# 05_LCD_LVDS.net
KiCad netlist of a schematic drawn in Altium Designer
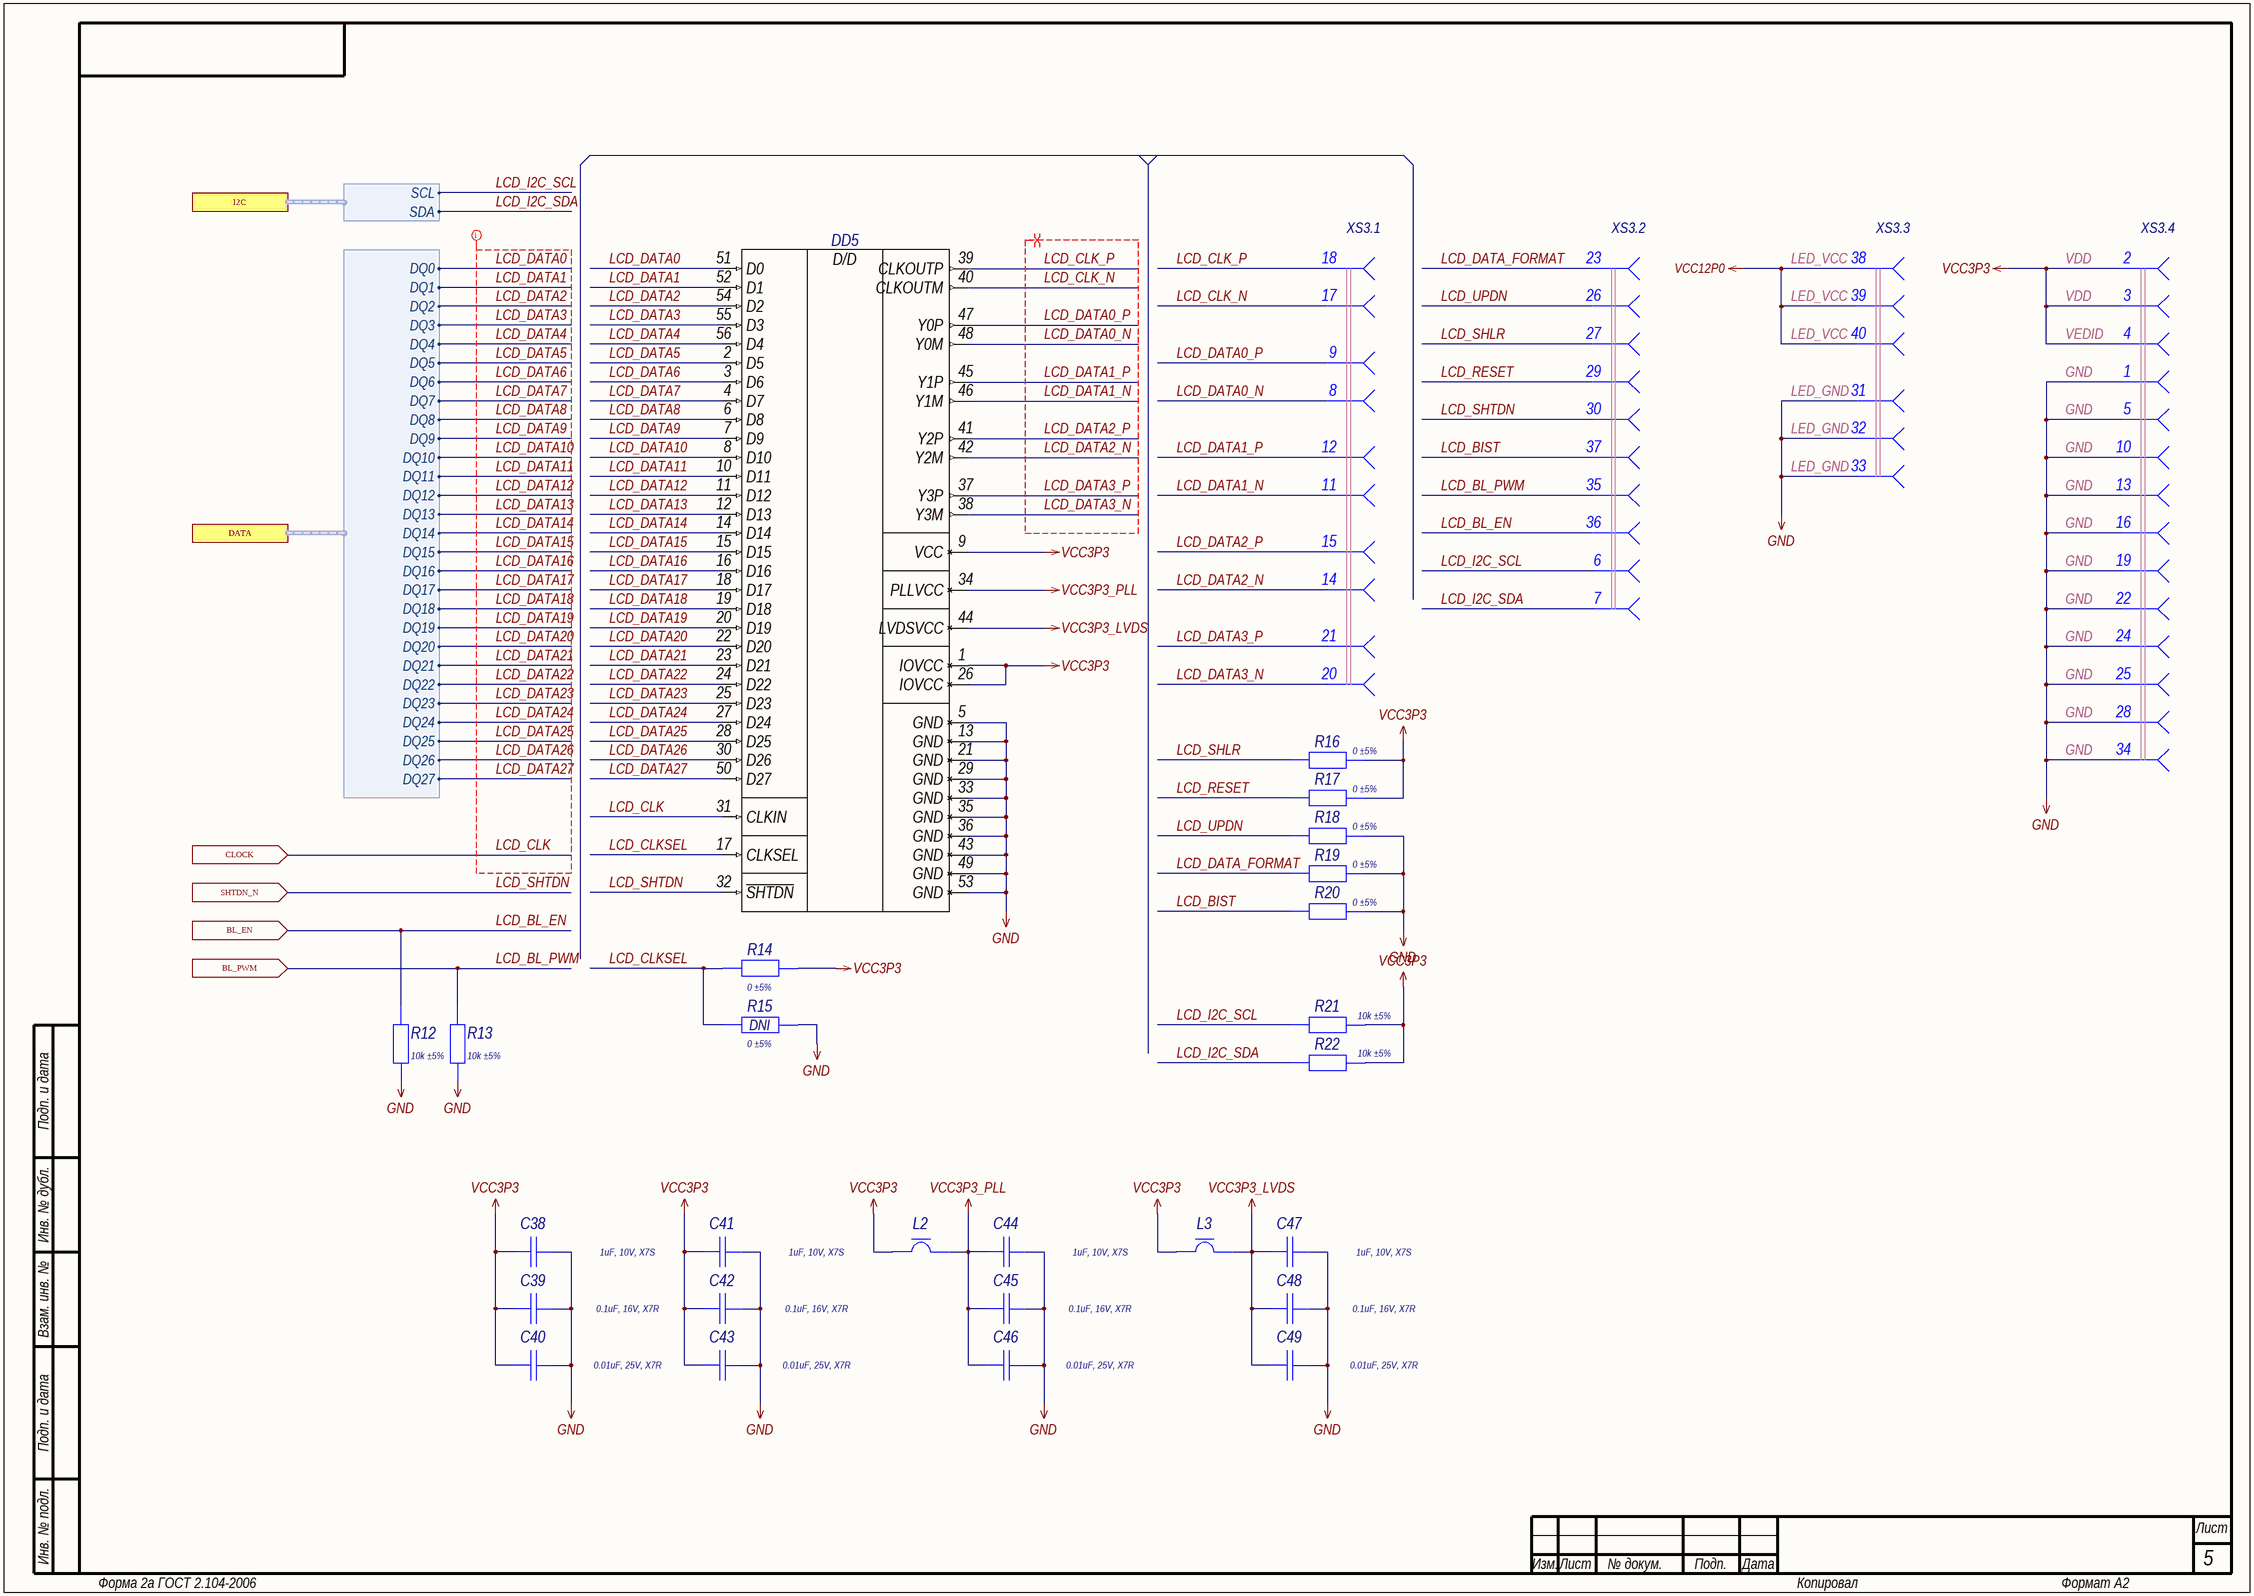
[diagram p0: 05_LCD_LVDS.SchDoc]

(export (version "E")
  (design (tool "Eeschema 10.0.6"))
  (components
    (comp (ref "C38")
      (value "Capacitor")
      (footprint "C0402_L")
      (fields
        (field (name "SCHEMATIC VALUE") "1uF, 10V, X7S")
        (field (name "PART NUMBER") "GRM155C71A105KE11D")
        (field (name "VOLTAGE") "10V")
        (field (name "TOLERANCE") "±10%")
        (field (name "PUBLISHER") "Andrew Danich")
      )
      (libsource (lib "ADLib") (part "Capacitor"))
    )
    (comp (ref "C39")
      (value "Capacitor")
      (footprint "C0402_L")
      (fields
        (field (name "SCHEMATIC VALUE") "0.1uF, 16V, X7R")
        (field (name "PART NUMBER") "GCM155R71C104KA55D")
        (field (name "VOLTAGE") "16V")
        (field (name "TOLERANCE") "±10%")
        (field (name "PUBLISHER") "Andrew Danich")
      )
      (libsource (lib "ADLib") (part "Capacitor"))
    )
    (comp (ref "C40")
      (value "Capacitor")
      (footprint "C0402_L")
      (fields
        (field (name "SCHEMATIC VALUE") "0.01uF, 25V, X7R")
        (field (name "PART NUMBER") "GCM155R71E103KA37D")
        (field (name "VOLTAGE") "25V")
        (field (name "TOLERANCE") "±10%")
        (field (name "PUBLISHER") "Andrew Danich")
      )
      (libsource (lib "ADLib") (part "Capacitor"))
    )
    (comp (ref "C41")
      (value "Capacitor")
      (footprint "C0402_L")
      (fields
        (field (name "SCHEMATIC VALUE") "1uF, 10V, X7S")
        (field (name "PART NUMBER") "GRM155C71A105KE11D")
        (field (name "VOLTAGE") "10V")
        (field (name "TOLERANCE") "±10%")
        (field (name "PUBLISHER") "Andrew Danich")
      )
      (libsource (lib "ADLib") (part "Capacitor"))
    )
    (comp (ref "C42")
      (value "Capacitor")
      (footprint "C0402_L")
      (fields
        (field (name "SCHEMATIC VALUE") "0.1uF, 16V, X7R")
        (field (name "PART NUMBER") "GCM155R71C104KA55D")
        (field (name "VOLTAGE") "16V")
        (field (name "TOLERANCE") "±10%")
        (field (name "PUBLISHER") "Andrew Danich")
      )
      (libsource (lib "ADLib") (part "Capacitor"))
    )
    (comp (ref "C43")
      (value "Capacitor")
      (footprint "C0402_L")
      (fields
        (field (name "SCHEMATIC VALUE") "0.01uF, 25V, X7R")
        (field (name "PART NUMBER") "GCM155R71E103KA37D")
        (field (name "VOLTAGE") "25V")
        (field (name "TOLERANCE") "±10%")
        (field (name "PUBLISHER") "Andrew Danich")
      )
      (libsource (lib "ADLib") (part "Capacitor"))
    )
    (comp (ref "C44")
      (value "Capacitor")
      (footprint "C0402_L")
      (fields
        (field (name "SCHEMATIC VALUE") "1uF, 10V, X7S")
        (field (name "PART NUMBER") "GRM155C71A105KE11D")
        (field (name "VOLTAGE") "10V")
        (field (name "TOLERANCE") "±10%")
        (field (name "PUBLISHER") "Andrew Danich")
      )
      (libsource (lib "ADLib") (part "Capacitor"))
    )
    (comp (ref "C45")
      (value "Capacitor")
      (footprint "C0402_L")
      (fields
        (field (name "SCHEMATIC VALUE") "0.1uF, 16V, X7R")
        (field (name "PART NUMBER") "GCM155R71C104KA55D")
        (field (name "VOLTAGE") "16V")
        (field (name "TOLERANCE") "±10%")
        (field (name "PUBLISHER") "Andrew Danich")
      )
      (libsource (lib "ADLib") (part "Capacitor"))
    )
    (comp (ref "C46")
      (value "Capacitor")
      (footprint "C0402_L")
      (fields
        (field (name "SCHEMATIC VALUE") "0.01uF, 25V, X7R")
        (field (name "PART NUMBER") "GCM155R71E103KA37D")
        (field (name "VOLTAGE") "25V")
        (field (name "TOLERANCE") "±10%")
        (field (name "PUBLISHER") "Andrew Danich")
      )
      (libsource (lib "ADLib") (part "Capacitor"))
    )
    (comp (ref "C47")
      (value "Capacitor")
      (footprint "C0402_L")
      (fields
        (field (name "SCHEMATIC VALUE") "1uF, 10V, X7S")
        (field (name "PART NUMBER") "GRM155C71A105KE11D")
        (field (name "VOLTAGE") "10V")
        (field (name "TOLERANCE") "±10%")
        (field (name "PUBLISHER") "Andrew Danich")
      )
      (libsource (lib "ADLib") (part "Capacitor"))
    )
    (comp (ref "C48")
      (value "Capacitor")
      (footprint "C0402_L")
      (fields
        (field (name "SCHEMATIC VALUE") "0.1uF, 16V, X7R")
        (field (name "PART NUMBER") "GCM155R71C104KA55D")
        (field (name "VOLTAGE") "16V")
        (field (name "TOLERANCE") "±10%")
        (field (name "PUBLISHER") "Andrew Danich")
      )
      (libsource (lib "ADLib") (part "Capacitor"))
    )
    (comp (ref "C49")
      (value "Capacitor")
      (footprint "C0402_L")
      (fields
        (field (name "SCHEMATIC VALUE") "0.01uF, 25V, X7R")
        (field (name "PART NUMBER") "GCM155R71E103KA37D")
        (field (name "VOLTAGE") "25V")
        (field (name "TOLERANCE") "±10%")
        (field (name "PUBLISHER") "Andrew Danich")
      )
      (libsource (lib "ADLib") (part "Capacitor"))
    )
    (comp (ref "DD5")
      (value "SN65LVDS93ADGG")
      (footprint "TSSOP-56_050P1400X610X120_N")
      (fields
        (field (name "PART NUMBER") "SN65LVDS93ADGGR")
        (field (name "MANUFACTURER") "Texas Instruments")
        (field (name "PUBLISHER") "Andrew Danich")
      )
      (libsource (lib "ADLib") (part "SN65LVDS93ADGG"))
    )
    (comp (ref "L2")
      (value "FerriteBead")
      (footprint "L0402_L")
      (fields
        (field (name "PART NUMBER") "BLM15PD121SN1D")
        (field (name "TOLERANCE") "±25%")
        (field (name "MANUFACTURER") "Murata")
        (field (name "PUBLISHER") "Andrew Danich")
      )
      (libsource (lib "ADLib") (part "FerriteBead"))
    )
    (comp (ref "L3")
      (value "FerriteBead")
      (footprint "L0402_L")
      (fields
        (field (name "PART NUMBER") "BLM15PD121SN1D")
        (field (name "TOLERANCE") "±25%")
        (field (name "MANUFACTURER") "Murata")
        (field (name "PUBLISHER") "Andrew Danich")
      )
      (libsource (lib "ADLib") (part "FerriteBead"))
    )
    (comp (ref "R12")
      (value "Resistor")
      (footprint "R0402_L")
      (fields
        (field (name "SCHEMATIC VALUE") "10k ±5%")
        (field (name "PART NUMBER") "RC0402JR-0710KL")
        (field (name "TOLERANCE") "±5%")
        (field (name "MANUFACTURER") "Yageo")
        (field (name "PUBLISHER") "Andrew Danich")
      )
      (libsource (lib "ADLib") (part "Resistor"))
    )
    (comp (ref "R13")
      (value "Resistor")
      (footprint "R0402_L")
      (fields
        (field (name "SCHEMATIC VALUE") "10k ±5%")
        (field (name "PART NUMBER") "RC0402JR-0710KL")
        (field (name "TOLERANCE") "±5%")
        (field (name "MANUFACTURER") "Yageo")
        (field (name "PUBLISHER") "Andrew Danich")
      )
      (libsource (lib "ADLib") (part "Resistor"))
    )
    (comp (ref "R14")
      (value "Resistor")
      (footprint "R0402_L")
      (fields
        (field (name "SCHEMATIC VALUE") "0 ±5%")
        (field (name "PART NUMBER") "RC0402JR-070RL")
        (field (name "TOLERANCE") "±5%")
        (field (name "MANUFACTURER") "Yageo")
        (field (name "PUBLISHER") "Andrew Danich")
      )
      (libsource (lib "ADLib") (part "Resistor"))
    )
    (comp (ref "R15")
      (value "Resistor")
      (footprint "R0402_L")
      (fields
        (field (name "SCHEMATIC VALUE") "0 ±5%")
        (field (name "PART NUMBER") "RC0402JR-070RL")
        (field (name "TOLERANCE") "±5%")
        (field (name "MANUFACTURER") "Yageo")
        (field (name "PUBLISHER") "Andrew Danich")
      )
      (libsource (lib "ADLib") (part "Resistor"))
    )
    (comp (ref "R16")
      (value "Resistor")
      (footprint "R0402_L")
      (fields
        (field (name "SCHEMATIC VALUE") "0 ±5%")
        (field (name "PART NUMBER") "RC0402JR-070RL")
        (field (name "TOLERANCE") "±5%")
        (field (name "MANUFACTURER") "Yageo")
        (field (name "PUBLISHER") "Andrew Danich")
      )
      (libsource (lib "ADLib") (part "Resistor"))
    )
    (comp (ref "R17")
      (value "Resistor")
      (footprint "R0402_L")
      (fields
        (field (name "SCHEMATIC VALUE") "0 ±5%")
        (field (name "PART NUMBER") "RC0402JR-070RL")
        (field (name "TOLERANCE") "±5%")
        (field (name "MANUFACTURER") "Yageo")
        (field (name "PUBLISHER") "Andrew Danich")
      )
      (libsource (lib "ADLib") (part "Resistor"))
    )
    (comp (ref "R18")
      (value "Resistor")
      (footprint "R0402_L")
      (fields
        (field (name "SCHEMATIC VALUE") "0 ±5%")
        (field (name "PART NUMBER") "RC0402JR-070RL")
        (field (name "TOLERANCE") "±5%")
        (field (name "MANUFACTURER") "Yageo")
        (field (name "PUBLISHER") "Andrew Danich")
      )
      (libsource (lib "ADLib") (part "Resistor"))
    )
    (comp (ref "R19")
      (value "Resistor")
      (footprint "R0402_L")
      (fields
        (field (name "SCHEMATIC VALUE") "0 ±5%")
        (field (name "PART NUMBER") "RC0402JR-070RL")
        (field (name "TOLERANCE") "±5%")
        (field (name "MANUFACTURER") "Yageo")
        (field (name "PUBLISHER") "Andrew Danich")
      )
      (libsource (lib "ADLib") (part "Resistor"))
    )
    (comp (ref "R20")
      (value "Resistor")
      (footprint "R0402_L")
      (fields
        (field (name "SCHEMATIC VALUE") "0 ±5%")
        (field (name "PART NUMBER") "RC0402JR-070RL")
        (field (name "TOLERANCE") "±5%")
        (field (name "MANUFACTURER") "Yageo")
        (field (name "PUBLISHER") "Andrew Danich")
      )
      (libsource (lib "ADLib") (part "Resistor"))
    )
    (comp (ref "R21")
      (value "Resistor")
      (footprint "R0402_L")
      (fields
        (field (name "SCHEMATIC VALUE") "10k ±5%")
        (field (name "PART NUMBER") "RC0402JR-0710KL")
        (field (name "TOLERANCE") "±5%")
        (field (name "MANUFACTURER") "Yageo")
        (field (name "PUBLISHER") "Andrew Danich")
      )
      (libsource (lib "ADLib") (part "Resistor"))
    )
    (comp (ref "R22")
      (value "Resistor")
      (footprint "R0402_L")
      (fields
        (field (name "SCHEMATIC VALUE") "10k ±5%")
        (field (name "PART NUMBER") "RC0402JR-0710KL")
        (field (name "TOLERANCE") "±5%")
        (field (name "MANUFACTURER") "Yageo")
        (field (name "PUBLISHER") "Andrew Danich")
      )
      (libsource (lib "ADLib") (part "Resistor"))
    )
    (comp (ref "XS3")
      (value "TFT LVDS")
      (footprint "54104-4031")
      (fields
        (field (name "PART NUMBER") "54104-4031")
        (field (name "MANUFACTURER") "Molex")
        (field (name "PUBLISHER") "Andrew Danich")
      )
      (libsource (lib "ADLib") (part "Con-40-F_S"))
    )
  )
  (nets
    (net (code "3") (name "/LCD_BIST") (class "Default")
      (node (ref "R20") (pin "1") (pinfunction "1_1") (pintype "passive"))
      (node (ref "XS3") (pin "37") (pintype "passive"))
    )
    (net (code "4") (name "/LCD_BL_EN") (class "Default")
      (node (ref "R12") (pin "2") (pinfunction "2_2") (pintype "passive"))
      (node (ref "XS3") (pin "36") (pintype "passive"))
    )
    (net (code "5") (name "/LCD_BL_PWM") (class "Default")
      (node (ref "R13") (pin "2") (pinfunction "2_2") (pintype "passive"))
      (node (ref "XS3") (pin "35") (pintype "passive"))
    )
    (net (code "6") (name "/LCD_CLK") (class "Default")
      (node (ref "DD5") (pin "31") (pinfunction "CLKIN_31") (pintype "input"))
    )
    (net (code "7") (name "/LCD_CLKSEL") (class "Default")
      (node (ref "DD5") (pin "17") (pinfunction "CLKSEL_17") (pintype "input"))
      (node (ref "R14") (pin "1") (pinfunction "1_1") (pintype "passive"))
      (node (ref "R15") (pin "1") (pinfunction "1_1") (pintype "passive"))
    )
    (net (code "8") (name "/LCD_CLK_N") (class "Default")
      (node (ref "DD5") (pin "40") (pinfunction "CLKOUTM_40") (pintype "output"))
      (node (ref "XS3") (pin "17") (pintype "passive"))
    )
    (net (code "9") (name "/LCD_CLK_P") (class "Default")
      (node (ref "DD5") (pin "39") (pinfunction "CLKOUTP_39") (pintype "output"))
      (node (ref "XS3") (pin "18") (pintype "passive"))
    )
    (net (code "10") (name "/LCD_DATA0") (class "Default")
      (node (ref "DD5") (pin "51") (pinfunction "D0_51") (pintype "input"))
    )
    (net (code "11") (name "/LCD_DATA0_N") (class "Default")
      (node (ref "DD5") (pin "48") (pinfunction "Y0M_48") (pintype "output"))
      (node (ref "XS3") (pin "8") (pintype "passive"))
    )
    (net (code "12") (name "/LCD_DATA0_P") (class "Default")
      (node (ref "DD5") (pin "47") (pinfunction "Y0P_47") (pintype "output"))
      (node (ref "XS3") (pin "9") (pintype "passive"))
    )
    (net (code "13") (name "/LCD_DATA1") (class "Default")
      (node (ref "DD5") (pin "52") (pinfunction "D1_52") (pintype "input"))
    )
    (net (code "14") (name "/LCD_DATA1_N") (class "Default")
      (node (ref "DD5") (pin "46") (pinfunction "Y1M_46") (pintype "output"))
      (node (ref "XS3") (pin "11") (pintype "passive"))
    )
    (net (code "15") (name "/LCD_DATA1_P") (class "Default")
      (node (ref "DD5") (pin "45") (pinfunction "Y1P_45") (pintype "output"))
      (node (ref "XS3") (pin "12") (pintype "passive"))
    )
    (net (code "16") (name "/LCD_DATA2") (class "Default")
      (node (ref "DD5") (pin "54") (pinfunction "D2_54") (pintype "input"))
    )
    (net (code "17") (name "/LCD_DATA2_N") (class "Default")
      (node (ref "DD5") (pin "42") (pinfunction "Y2M_42") (pintype "output"))
      (node (ref "XS3") (pin "14") (pintype "passive"))
    )
    (net (code "18") (name "/LCD_DATA2_P") (class "Default")
      (node (ref "DD5") (pin "41") (pinfunction "Y2P_41") (pintype "output"))
      (node (ref "XS3") (pin "15") (pintype "passive"))
    )
    (net (code "19") (name "/LCD_DATA3") (class "Default")
      (node (ref "DD5") (pin "55") (pinfunction "D3_55") (pintype "input"))
    )
    (net (code "20") (name "/LCD_DATA3_N") (class "Default")
      (node (ref "DD5") (pin "38") (pinfunction "Y3M_38") (pintype "output"))
      (node (ref "XS3") (pin "20") (pintype "passive"))
    )
    (net (code "21") (name "/LCD_DATA3_P") (class "Default")
      (node (ref "DD5") (pin "37") (pinfunction "Y3P_37") (pintype "output"))
      (node (ref "XS3") (pin "21") (pintype "passive"))
    )
    (net (code "22") (name "/LCD_DATA4") (class "Default")
      (node (ref "DD5") (pin "56") (pinfunction "D4_56") (pintype "input"))
    )
    (net (code "23") (name "/LCD_DATA5") (class "Default")
      (node (ref "DD5") (pin "2") (pinfunction "D5_2") (pintype "input"))
    )
    (net (code "24") (name "/LCD_DATA6") (class "Default")
      (node (ref "DD5") (pin "3") (pinfunction "D6_3") (pintype "input"))
    )
    (net (code "25") (name "/LCD_DATA7") (class "Default")
      (node (ref "DD5") (pin "4") (pinfunction "D7_4") (pintype "input"))
    )
    (net (code "26") (name "/LCD_DATA8") (class "Default")
      (node (ref "DD5") (pin "6") (pinfunction "D8_6") (pintype "input"))
    )
    (net (code "27") (name "/LCD_DATA9") (class "Default")
      (node (ref "DD5") (pin "7") (pinfunction "D9_7") (pintype "input"))
    )
    (net (code "28") (name "/LCD_DATA10") (class "Default")
      (node (ref "DD5") (pin "8") (pinfunction "D10_8") (pintype "input"))
    )
    (net (code "29") (name "/LCD_DATA11") (class "Default")
      (node (ref "DD5") (pin "10") (pinfunction "D11_10") (pintype "input"))
    )
    (net (code "30") (name "/LCD_DATA12") (class "Default")
      (node (ref "DD5") (pin "11") (pinfunction "D12_11") (pintype "input"))
    )
    (net (code "31") (name "/LCD_DATA13") (class "Default")
      (node (ref "DD5") (pin "12") (pinfunction "D13_12") (pintype "input"))
    )
    (net (code "32") (name "/LCD_DATA14") (class "Default")
      (node (ref "DD5") (pin "14") (pinfunction "D14_14") (pintype "input"))
    )
    (net (code "33") (name "/LCD_DATA15") (class "Default")
      (node (ref "DD5") (pin "15") (pinfunction "D15_15") (pintype "input"))
    )
    (net (code "34") (name "/LCD_DATA16") (class "Default")
      (node (ref "DD5") (pin "16") (pinfunction "D16_16") (pintype "input"))
    )
    (net (code "35") (name "/LCD_DATA17") (class "Default")
      (node (ref "DD5") (pin "18") (pinfunction "D17_18") (pintype "input"))
    )
    (net (code "36") (name "/LCD_DATA18") (class "Default")
      (node (ref "DD5") (pin "19") (pinfunction "D18_19") (pintype "input"))
    )
    (net (code "37") (name "/LCD_DATA19") (class "Default")
      (node (ref "DD5") (pin "20") (pinfunction "D19_20") (pintype "input"))
    )
    (net (code "38") (name "/LCD_DATA20") (class "Default")
      (node (ref "DD5") (pin "22") (pinfunction "D20_22") (pintype "input"))
    )
    (net (code "39") (name "/LCD_DATA21") (class "Default")
      (node (ref "DD5") (pin "23") (pinfunction "D21_23") (pintype "input"))
    )
    (net (code "40") (name "/LCD_DATA22") (class "Default")
      (node (ref "DD5") (pin "24") (pinfunction "D22_24") (pintype "input"))
    )
    (net (code "41") (name "/LCD_DATA23") (class "Default")
      (node (ref "DD5") (pin "25") (pinfunction "D23_25") (pintype "input"))
    )
    (net (code "42") (name "/LCD_DATA24") (class "Default")
      (node (ref "DD5") (pin "27") (pinfunction "D24_27") (pintype "input"))
    )
    (net (code "43") (name "/LCD_DATA25") (class "Default")
      (node (ref "DD5") (pin "28") (pinfunction "D25_28") (pintype "input"))
    )
    (net (code "44") (name "/LCD_DATA26") (class "Default")
      (node (ref "DD5") (pin "30") (pinfunction "D26_30") (pintype "input"))
    )
    (net (code "45") (name "/LCD_DATA27") (class "Default")
      (node (ref "DD5") (pin "50") (pinfunction "D27_50") (pintype "input"))
    )
    (net (code "46") (name "/LCD_DATA_FORMAT") (class "Default")
      (node (ref "R19") (pin "1") (pinfunction "1_1") (pintype "passive"))
      (node (ref "XS3") (pin "23") (pintype "passive"))
    )
    (net (code "47") (name "/LCD_I2C_SCL") (class "Default")
      (node (ref "R21") (pin "2") (pinfunction "2_2") (pintype "passive"))
      (node (ref "XS3") (pin "6") (pintype "passive"))
    )
    (net (code "48") (name "/LCD_I2C_SDA") (class "Default")
      (node (ref "R22") (pin "2") (pinfunction "2_2") (pintype "passive"))
      (node (ref "XS3") (pin "7") (pintype "passive"))
    )
    (net (code "49") (name "/LCD_RESET") (class "Default")
      (node (ref "R17") (pin "1") (pinfunction "1_1") (pintype "passive"))
      (node (ref "XS3") (pin "29") (pintype "passive"))
    )
    (net (code "50") (name "/LCD_SHLR") (class "Default")
      (node (ref "R16") (pin "1") (pinfunction "1_1") (pintype "passive"))
      (node (ref "XS3") (pin "27") (pintype "passive"))
    )
    (net (code "51") (name "/LCD_SHTDN") (class "Default")
      (node (ref "DD5") (pin "32") (pinfunction "~{SHTDN}_32") (pintype "input"))
      (node (ref "XS3") (pin "30") (pintype "passive"))
    )
    (net (code "52") (name "/LCD_UPDN") (class "Default")
      (node (ref "R18") (pin "1") (pinfunction "1_1") (pintype "passive"))
      (node (ref "XS3") (pin "26") (pintype "passive"))
    )
    (net (code "55") (name "GND") (class "Default")
      (node (ref "C38") (pin "2") (pinfunction "2_2") (pintype "passive"))
      (node (ref "C39") (pin "2") (pinfunction "2_2") (pintype "passive"))
      (node (ref "C40") (pin "2") (pinfunction "2_2") (pintype "passive"))
      (node (ref "C41") (pin "2") (pinfunction "2_2") (pintype "passive"))
      (node (ref "C42") (pin "2") (pinfunction "2_2") (pintype "passive"))
      (node (ref "C43") (pin "2") (pinfunction "2_2") (pintype "passive"))
      (node (ref "C44") (pin "2") (pinfunction "2_2") (pintype "passive"))
      (node (ref "C45") (pin "2") (pinfunction "2_2") (pintype "passive"))
      (node (ref "C46") (pin "2") (pinfunction "2_2") (pintype "passive"))
      (node (ref "C47") (pin "2") (pinfunction "2_2") (pintype "passive"))
      (node (ref "C48") (pin "2") (pinfunction "2_2") (pintype "passive"))
      (node (ref "C49") (pin "2") (pinfunction "2_2") (pintype "passive"))
      (node (ref "DD5") (pin "13") (pinfunction "GND_13") (pintype "power_in"))
      (node (ref "DD5") (pin "21") (pinfunction "GND_21") (pintype "power_in"))
      (node (ref "DD5") (pin "29") (pinfunction "GND_29") (pintype "power_in"))
      (node (ref "DD5") (pin "33") (pinfunction "GND_33") (pintype "power_in"))
      (node (ref "DD5") (pin "35") (pinfunction "GND_35") (pintype "power_in"))
      (node (ref "DD5") (pin "36") (pinfunction "GND_36") (pintype "power_in"))
      (node (ref "DD5") (pin "43") (pinfunction "GND_43") (pintype "power_in"))
      (node (ref "DD5") (pin "49") (pinfunction "GND_49") (pintype "power_in"))
      (node (ref "DD5") (pin "5") (pinfunction "GND_5") (pintype "power_in"))
      (node (ref "DD5") (pin "53") (pinfunction "GND_53") (pintype "power_in"))
      (node (ref "R12") (pin "1") (pinfunction "1_1") (pintype "passive"))
      (node (ref "R13") (pin "1") (pinfunction "1_1") (pintype "passive"))
      (node (ref "R15") (pin "2") (pinfunction "2_2") (pintype "passive"))
      (node (ref "R18") (pin "2") (pinfunction "2_2") (pintype "passive"))
      (node (ref "R19") (pin "2") (pinfunction "2_2") (pintype "passive"))
      (node (ref "R20") (pin "2") (pinfunction "2_2") (pintype "passive"))
      (node (ref "XS3") (pin "1") (pintype "passive"))
      (node (ref "XS3") (pin "10") (pintype "passive"))
      (node (ref "XS3") (pin "13") (pintype "passive"))
      (node (ref "XS3") (pin "16") (pintype "passive"))
      (node (ref "XS3") (pin "19") (pintype "passive"))
      (node (ref "XS3") (pin "22") (pintype "passive"))
      (node (ref "XS3") (pin "24") (pintype "passive"))
      (node (ref "XS3") (pin "25") (pintype "passive"))
      (node (ref "XS3") (pin "28") (pintype "passive"))
      (node (ref "XS3") (pin "31") (pintype "passive"))
      (node (ref "XS3") (pin "32") (pintype "passive"))
      (node (ref "XS3") (pin "33") (pintype "passive"))
      (node (ref "XS3") (pin "34") (pintype "passive"))
      (node (ref "XS3") (pin "5") (pintype "passive"))
    )
    (net (code "56") (name "VCC3P3") (class "Default")
      (node (ref "C38") (pin "1") (pinfunction "1_1") (pintype "passive"))
      (node (ref "C39") (pin "1") (pinfunction "1_1") (pintype "passive"))
      (node (ref "C40") (pin "1") (pinfunction "1_1") (pintype "passive"))
      (node (ref "C41") (pin "1") (pinfunction "1_1") (pintype "passive"))
      (node (ref "C42") (pin "1") (pinfunction "1_1") (pintype "passive"))
      (node (ref "C43") (pin "1") (pinfunction "1_1") (pintype "passive"))
      (node (ref "DD5") (pin "1") (pinfunction "IOVCC_1") (pintype "power_in"))
      (node (ref "DD5") (pin "26") (pinfunction "IOVCC_26") (pintype "power_in"))
      (node (ref "DD5") (pin "9") (pinfunction "VCC_9") (pintype "power_in"))
      (node (ref "L2") (pin "1") (pinfunction "1_1") (pintype "passive"))
      (node (ref "L3") (pin "1") (pinfunction "1_1") (pintype "passive"))
      (node (ref "R14") (pin "2") (pinfunction "2_2") (pintype "passive"))
      (node (ref "R16") (pin "2") (pinfunction "2_2") (pintype "passive"))
      (node (ref "R17") (pin "2") (pinfunction "2_2") (pintype "passive"))
      (node (ref "R21") (pin "1") (pinfunction "1_1") (pintype "passive"))
      (node (ref "R22") (pin "1") (pinfunction "1_1") (pintype "passive"))
      (node (ref "XS3") (pin "2") (pintype "passive"))
      (node (ref "XS3") (pin "3") (pintype "passive"))
      (node (ref "XS3") (pin "4") (pintype "passive"))
    )
    (net (code "57") (name "VCC3P3_LVDS") (class "Default")
      (node (ref "C47") (pin "1") (pinfunction "1_1") (pintype "passive"))
      (node (ref "C48") (pin "1") (pinfunction "1_1") (pintype "passive"))
      (node (ref "C49") (pin "1") (pinfunction "1_1") (pintype "passive"))
      (node (ref "DD5") (pin "44") (pinfunction "LVDSVCC_44") (pintype "power_in"))
      (node (ref "L3") (pin "2") (pinfunction "2_2") (pintype "passive"))
    )
    (net (code "58") (name "VCC3P3_PLL") (class "Default")
      (node (ref "C44") (pin "1") (pinfunction "1_1") (pintype "passive"))
      (node (ref "C45") (pin "1") (pinfunction "1_1") (pintype "passive"))
      (node (ref "C46") (pin "1") (pinfunction "1_1") (pintype "passive"))
      (node (ref "DD5") (pin "34") (pinfunction "PLLVCC_34") (pintype "power_in"))
      (node (ref "L2") (pin "2") (pinfunction "2_2") (pintype "passive"))
    )
    (net (code "59") (name "VCC12P0") (class "Default")
      (node (ref "XS3") (pin "38") (pintype "passive"))
      (node (ref "XS3") (pin "39") (pintype "passive"))
      (node (ref "XS3") (pin "40") (pintype "passive"))
    )
  )
)
